# 05-UART.net
KiCad netlist of a schematic drawn in Altium Designer
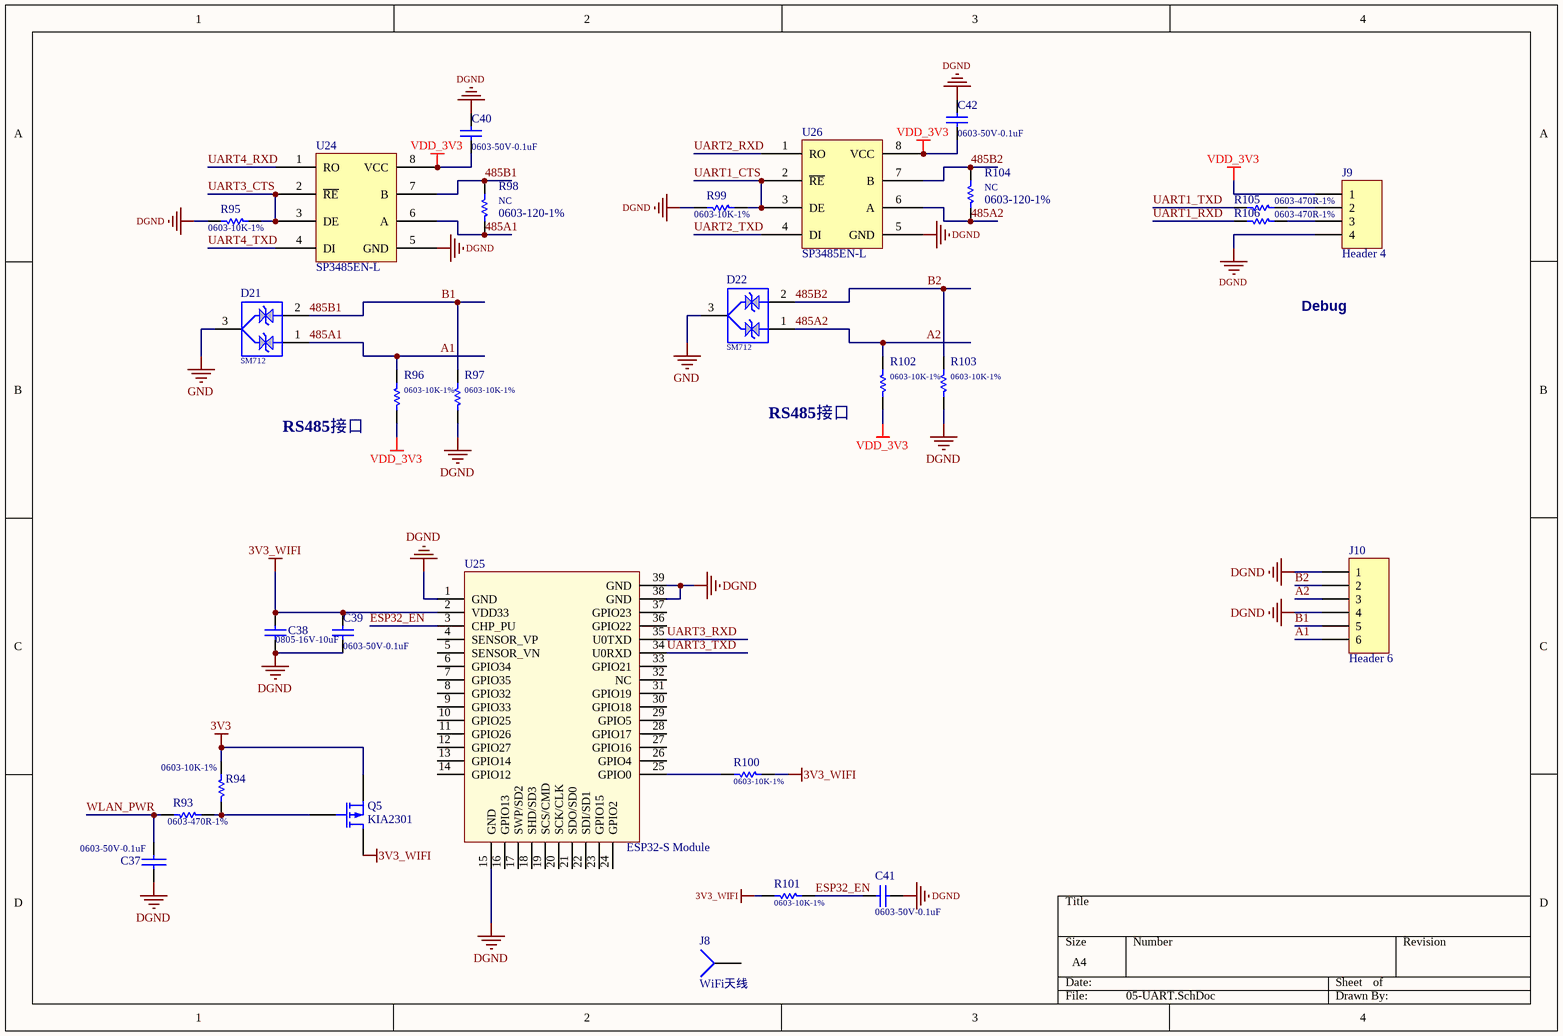
[diagram p0: 05-UART.SchDoc]

(export (version "E")
  (design (tool "Eeschema 10.0.6"))
  (components
    (comp (ref "C37")
      (value "0603-50V-0.1uF")
      (footprint "0603C")
      (description "Capacitor")
      (libsource (lib "*") (part "CAP"))
    )
    (comp (ref "C38")
      (value "0805-16V-10uF")
      (footprint "0805C - 3D")
      (description "Capacitor")
      (fields (field (name "PUBLISHER") "Altium Limited"))
      (libsource (lib "Miscellaneous Devices") (part "Cap"))
    )
    (comp (ref "C39")
      (value "0603-50V-0.1uF")
      (footprint "0603C")
      (description "Capacitor")
      (fields (field (name "PUBLISHER") "Altium Limited"))
      (libsource (lib "Miscellaneous Devices") (part "Cap"))
    )
    (comp (ref "C40")
      (value "0603-50V-0.1uF")
      (footprint "0603C")
      (description "Capacitor")
      (fields (field (name "PUBLISHER") "Altium Limited"))
      (libsource (lib "Miscellaneous Devices") (part "Cap"))
    )
    (comp (ref "C41")
      (value "0603-50V-0.1uF")
      (footprint "0603C")
      (description "Capacitor")
      (fields (field (name "PUBLISHER") "Altium Limited"))
      (libsource (lib "Miscellaneous Devices") (part "Cap"))
    )
    (comp (ref "C42")
      (value "0603-50V-0.1uF")
      (footprint "0603C")
      (description "Capacitor")
      (fields (field (name "PUBLISHER") "Altium Limited"))
      (libsource (lib "Miscellaneous Devices") (part "Cap"))
    )
    (comp (ref "D21")
      (value "SM712")
      (footprint "SOT-23")
      (description "TVS protect")
      (libsource (lib "*") (part "NUP2105L"))
    )
    (comp (ref "D22")
      (value "SM712")
      (footprint "SOT-23")
      (description "TVS protect")
      (libsource (lib "*") (part "NUP2105L"))
    )
    (comp (ref "J8")
      (value "WiFi天线")
      (footprint "SMA-KWE")
      (description "Socket")
      (fields (field (name "PUBLISHER") "Altium Limited"))
      (libsource (lib "Miscellaneous Connectors") (part "Socket"))
    )
    (comp (ref "J9")
      (value "Header 4")
      (footprint "HDR1X4")
      (description "Header, 4-Pin")
      (fields (field (name "PUBLISHER") "Altium Limited"))
      (libsource (lib "Miscellaneous Connectors") (part "Header 4"))
    )
    (comp (ref "J10")
      (value "Header 6")
      (footprint "KF2EDGR-5.08-6P")
      (description "Header, 6-Pin")
      (fields (field (name "PUBLISHER") "Altium Limited"))
      (libsource (lib "Miscellaneous Connectors") (part "Header 6"))
    )
    (comp (ref "Q5")
      (value "KIA2301")
      (footprint "SOT-23")
      (description "P-Channel MOSFET")
      (fields (field (name "PUBLISHER") "Altium Limited"))
      (libsource (lib "fszhang") (part "MOSFET-P"))
    )
    (comp (ref "R93")
      (value "0603-470R-1%")
      (footprint "0603R")
      (description "Resistor")
      (fields (field (name "PUBLISHER") "Altium Limited"))
      (libsource (lib "Miscellaneous Devices") (part "Res1"))
    )
    (comp (ref "R94")
      (value "0603-10K-1%")
      (footprint "0603R")
      (description "Resistor")
      (fields (field (name "PUBLISHER") "Altium Limited"))
      (libsource (lib "Miscellaneous Devices") (part "Res1"))
    )
    (comp (ref "R95")
      (value "0603-10K-1%")
      (footprint "0603R")
      (description "Resistor")
      (fields (field (name "PUBLISHER") "Altium Limited"))
      (libsource (lib "Miscellaneous Devices") (part "Res1"))
    )
    (comp (ref "R96")
      (value "0603-10K-1%")
      (footprint "0603R")
      (description "Resistor")
      (fields (field (name "PUBLISHER") "Altium Limited"))
      (libsource (lib "Miscellaneous Devices") (part "Res1"))
    )
    (comp (ref "R97")
      (value "0603-10K-1%")
      (footprint "0603R")
      (description "Resistor")
      (fields (field (name "PUBLISHER") "Altium Limited"))
      (libsource (lib "Miscellaneous Devices") (part "Res1"))
    )
    (comp (ref "R98")
      (value "NC")
      (footprint "0603R")
      (description "Resistor")
      (fields (field (name "ALTIUM_VALUE") "0603-120-1%") (field (name "PUBLISHER") "Altium Limited"))
      (libsource (lib "Miscellaneous Devices") (part "Res1"))
    )
    (comp (ref "R99")
      (value "0603-10K-1%")
      (footprint "0603R")
      (description "Resistor")
      (fields (field (name "PUBLISHER") "Altium Limited"))
      (libsource (lib "Miscellaneous Devices") (part "Res1"))
    )
    (comp (ref "R100")
      (value "0603-10K-1%")
      (footprint "0603R")
      (description "Resistor")
      (fields (field (name "PUBLISHER") "Altium Limited"))
      (libsource (lib "Miscellaneous Devices") (part "Res1"))
    )
    (comp (ref "R101")
      (value "0603-10K-1%")
      (footprint "0603R")
      (description "Resistor")
      (fields (field (name "PUBLISHER") "Altium Limited"))
      (libsource (lib "Miscellaneous Devices") (part "Res1"))
    )
    (comp (ref "R102")
      (value "0603-10K-1%")
      (footprint "0603R")
      (description "Resistor")
      (fields (field (name "PUBLISHER") "Altium Limited"))
      (libsource (lib "Miscellaneous Devices") (part "Res1"))
    )
    (comp (ref "R103")
      (value "0603-10K-1%")
      (footprint "0603R")
      (description "Resistor")
      (fields (field (name "PUBLISHER") "Altium Limited"))
      (libsource (lib "Miscellaneous Devices") (part "Res1"))
    )
    (comp (ref "R104")
      (value "NC")
      (footprint "0603R")
      (description "Resistor")
      (fields (field (name "ALTIUM_VALUE") "0603-120-1%") (field (name "PUBLISHER") "Altium Limited"))
      (libsource (lib "Miscellaneous Devices") (part "Res1"))
    )
    (comp (ref "R105")
      (value "0603-470R-1%")
      (footprint "0603R")
      (description "Resistor")
      (fields (field (name "PUBLISHER") "Altium Limited"))
      (libsource (lib "Miscellaneous Devices") (part "Res1"))
    )
    (comp (ref "R106")
      (value "0603-470R-1%")
      (footprint "0603R")
      (description "Resistor")
      (fields (field (name "PUBLISHER") "Altium Limited"))
      (libsource (lib "Miscellaneous Devices") (part "Res1"))
    )
    (comp (ref "U24")
      (value "SP3485EN-L")
      (footprint "LC-SOIC-8_150mil")
      (libsource (lib "金龙107原理图封装库") (part "MAX485"))
    )
    (comp (ref "U25")
      (value "ESP32-S Module")
      (footprint "ESP32S")
      (libsource (lib "ESP32-S Module") (part "ESP32-S Module"))
    )
    (comp (ref "U26")
      (value "SP3485EN-L")
      (footprint "LC-SOIC-8_150mil")
      (libsource (lib "金龙107原理图封装库") (part "MAX485"))
    )
  )
  (nets
    (net (code "1") (name "/485A1") (class "Default")
      (node (ref "D21") (pin "1") (pinfunction "1_1") (pintype "passive"))
      (node (ref "J10") (pin "6") (pinfunction "6_6") (pintype "passive"))
      (node (ref "R96") (pin "1") (pinfunction "1_1") (pintype "passive"))
      (node (ref "R98") (pin "2") (pinfunction "2_2") (pintype "passive"))
      (node (ref "U24") (pin "6") (pinfunction "A_6") (pintype "open_emitter"))
    )
    (net (code "2") (name "/485A2") (class "Default")
      (node (ref "D22") (pin "1") (pinfunction "1_1") (pintype "passive"))
      (node (ref "J10") (pin "3") (pinfunction "3_3") (pintype "passive"))
      (node (ref "R102") (pin "1") (pinfunction "1_1") (pintype "passive"))
      (node (ref "R104") (pin "2") (pinfunction "2_2") (pintype "passive"))
      (node (ref "U26") (pin "6") (pinfunction "A_6") (pintype "open_emitter"))
    )
    (net (code "3") (name "/485B1") (class "Default")
      (node (ref "D21") (pin "2") (pinfunction "2_2") (pintype "passive"))
      (node (ref "J10") (pin "5") (pinfunction "5_5") (pintype "passive"))
      (node (ref "R97") (pin "1") (pinfunction "1_1") (pintype "passive"))
      (node (ref "R98") (pin "1") (pinfunction "1_1") (pintype "passive"))
      (node (ref "U24") (pin "7") (pinfunction "B_7") (pintype "open_emitter"))
    )
    (net (code "4") (name "/485B2") (class "Default")
      (node (ref "D22") (pin "2") (pinfunction "2_2") (pintype "passive"))
      (node (ref "J10") (pin "2") (pinfunction "2_2") (pintype "passive"))
      (node (ref "R103") (pin "1") (pinfunction "1_1") (pintype "passive"))
      (node (ref "R104") (pin "1") (pinfunction "1_1") (pintype "passive"))
      (node (ref "U26") (pin "7") (pinfunction "B_7") (pintype "open_emitter"))
    )
    (net (code "5") (name "/ESP32_EN") (class "Default")
      (node (ref "C41") (pin "1") (pinfunction "1_1") (pintype "passive"))
      (node (ref "R101") (pin "1") (pinfunction "1_1") (pintype "passive"))
      (node (ref "U25") (pin "3") (pinfunction "CHP_PU_3") (pintype "passive"))
    )
    (net (code "6") (name "/UART1_CTS") (class "Default")
      (node (ref "R99") (pin "1") (pinfunction "1_1") (pintype "passive"))
      (node (ref "U26") (pin "2") (pinfunction "~{RE}_2") (pintype "passive"))
      (node (ref "U26") (pin "3") (pinfunction "DE_3") (pintype "passive"))
    )
    (net (code "7") (name "/UART1_RXD") (class "Default")
      (node (ref "R106") (pin "2") (pinfunction "2_2") (pintype "passive"))
    )
    (net (code "8") (name "/UART1_TXD") (class "Default")
      (node (ref "R105") (pin "2") (pinfunction "2_2") (pintype "passive"))
    )
    (net (code "9") (name "/UART2_RXD") (class "Default")
      (node (ref "U26") (pin "1") (pinfunction "RO_1") (pintype "open_emitter"))
    )
    (net (code "10") (name "/UART2_TXD") (class "Default")
      (node (ref "U26") (pin "4") (pinfunction "DI_4") (pintype "passive"))
    )
    (net (code "11") (name "/UART3_CTS") (class "Default")
      (node (ref "R95") (pin "1") (pinfunction "1_1") (pintype "passive"))
      (node (ref "U24") (pin "2") (pinfunction "~{RE}_2") (pintype "passive"))
      (node (ref "U24") (pin "3") (pinfunction "DE_3") (pintype "passive"))
    )
    (net (code "12") (name "/UART3_RXD") (class "Default")
      (node (ref "U25") (pin "35") (pinfunction "U0TXD_35") (pintype "passive"))
    )
    (net (code "13") (name "/UART3_TXD") (class "Default")
      (node (ref "U25") (pin "34") (pinfunction "U0RXD_34") (pintype "passive"))
    )
    (net (code "14") (name "/UART4_RXD") (class "Default")
      (node (ref "U24") (pin "1") (pinfunction "RO_1") (pintype "open_emitter"))
    )
    (net (code "15") (name "/UART4_TXD") (class "Default")
      (node (ref "U24") (pin "4") (pinfunction "DI_4") (pintype "passive"))
    )
    (net (code "16") (name "/WLAN_PWR") (class "Default")
      (node (ref "C37") (pin "1") (pinfunction "1_1") (pintype "passive"))
      (node (ref "R93") (pin "2") (pinfunction "2_2") (pintype "passive"))
    )
    (net (code "17") (name "3V3") (class "Default")
      (node (ref "Q5") (pin "S") (pinfunction "S_S") (pintype "passive"))
      (node (ref "R94") (pin "1") (pinfunction "1_1") (pintype "passive"))
    )
    (net (code "18") (name "3V3_WIFI") (class "Default")
      (node (ref "C38") (pin "1") (pinfunction "1_1") (pintype "passive"))
      (node (ref "C39") (pin "1") (pinfunction "1_1") (pintype "passive"))
      (node (ref "Q5") (pin "D") (pinfunction "D_D") (pintype "passive"))
      (node (ref "R100") (pin "2") (pinfunction "2_2") (pintype "passive"))
      (node (ref "R101") (pin "2") (pinfunction "2_2") (pintype "passive"))
      (node (ref "U25") (pin "2") (pinfunction "VDD33_2") (pintype "passive"))
    )
    (net (code "19") (name "DGND") (class "Default")
      (node (ref "C37") (pin "2") (pinfunction "2_2") (pintype "passive"))
      (node (ref "C38") (pin "2") (pinfunction "2_2") (pintype "passive"))
      (node (ref "C39") (pin "2") (pinfunction "2_2") (pintype "passive"))
      (node (ref "C40") (pin "1") (pinfunction "1_1") (pintype "passive"))
      (node (ref "C41") (pin "2") (pinfunction "2_2") (pintype "passive"))
      (node (ref "C42") (pin "1") (pinfunction "1_1") (pintype "passive"))
      (node (ref "J10") (pin "1") (pinfunction "1_1") (pintype "passive"))
      (node (ref "J10") (pin "4") (pinfunction "4_4") (pintype "passive"))
      (node (ref "J9") (pin "4") (pinfunction "4_4") (pintype "passive"))
      (node (ref "R103") (pin "2") (pinfunction "2_2") (pintype "passive"))
      (node (ref "R95") (pin "2") (pinfunction "2_2") (pintype "passive"))
      (node (ref "R97") (pin "2") (pinfunction "2_2") (pintype "passive"))
      (node (ref "R99") (pin "2") (pinfunction "2_2") (pintype "passive"))
      (node (ref "U24") (pin "5") (pinfunction "GND_5") (pintype "passive"))
      (node (ref "U25") (pin "1") (pinfunction "GND_1") (pintype "passive"))
      (node (ref "U25") (pin "15") (pinfunction "GND_15") (pintype "passive"))
      (node (ref "U25") (pin "38") (pinfunction "GND_38") (pintype "passive"))
      (node (ref "U25") (pin "39") (pinfunction "GND_39") (pintype "passive"))
      (node (ref "U26") (pin "5") (pinfunction "GND_5") (pintype "passive"))
    )
    (net (code "20") (name "GND") (class "Default")
      (node (ref "D21") (pin "3") (pinfunction "3_3") (pintype "passive"))
      (node (ref "D22") (pin "3") (pinfunction "3_3") (pintype "passive"))
    )
    (net (code "21") (name "Net-(J9-Pad2)") (class "Default")
      (node (ref "J9") (pin "2") (pinfunction "2_2") (pintype "passive"))
      (node (ref "R105") (pin "1") (pinfunction "1_1") (pintype "passive"))
    )
    (net (code "22") (name "Net-(J9-Pad3)") (class "Default")
      (node (ref "J9") (pin "3") (pinfunction "3_3") (pintype "passive"))
      (node (ref "R106") (pin "1") (pinfunction "1_1") (pintype "passive"))
    )
    (net (code "23") (name "Net-(Q5-PadG)") (class "Default")
      (node (ref "Q5") (pin "G") (pinfunction "G_G") (pintype "passive"))
      (node (ref "R93") (pin "1") (pinfunction "1_1") (pintype "passive"))
      (node (ref "R94") (pin "2") (pinfunction "2_2") (pintype "passive"))
    )
    (net (code "24") (name "Net-(U25-GPIO0)") (class "Default")
      (node (ref "R100") (pin "1") (pinfunction "1_1") (pintype "passive"))
      (node (ref "U25") (pin "25") (pinfunction "GPIO0_25") (pintype "passive"))
    )
    (net (code "25") (name "VDD_3V3") (class "Default")
      (node (ref "C40") (pin "2") (pinfunction "2_2") (pintype "passive"))
      (node (ref "C42") (pin "2") (pinfunction "2_2") (pintype "passive"))
      (node (ref "J9") (pin "1") (pinfunction "1_1") (pintype "passive"))
      (node (ref "R102") (pin "2") (pinfunction "2_2") (pintype "passive"))
      (node (ref "R96") (pin "2") (pinfunction "2_2") (pintype "passive"))
      (node (ref "U24") (pin "8") (pinfunction "VCC_8") (pintype "passive"))
      (node (ref "U26") (pin "8") (pinfunction "VCC_8") (pintype "passive"))
    )
    (net (code "26") (name "unconnected-(J8-Pad1)") (class "Default")
      (node (ref "J8") (pin "1") (pinfunction "1_1") (pintype "passive"))
    )
    (net (code "27") (name "unconnected-(U25-GPIO2-Pad24)") (class "Default")
      (node (ref "U25") (pin "24") (pinfunction "GPIO2_24") (pintype "passive"))
    )
    (net (code "28") (name "unconnected-(U25-GPIO4-Pad26)") (class "Default")
      (node (ref "U25") (pin "26") (pinfunction "GPIO4_26") (pintype "passive"))
    )
    (net (code "29") (name "unconnected-(U25-GPIO5-Pad29)") (class "Default")
      (node (ref "U25") (pin "29") (pinfunction "GPIO5_29") (pintype "passive"))
    )
    (net (code "30") (name "unconnected-(U25-GPIO12-Pad14)") (class "Default")
      (node (ref "U25") (pin "14") (pinfunction "GPIO12_14") (pintype "passive"))
    )
    (net (code "31") (name "unconnected-(U25-GPIO13-Pad16)") (class "Default")
      (node (ref "U25") (pin "16") (pinfunction "GPIO13_16") (pintype "passive"))
    )
    (net (code "32") (name "unconnected-(U25-GPIO14-Pad13)") (class "Default")
      (node (ref "U25") (pin "13") (pinfunction "GPIO14_13") (pintype "passive"))
    )
    (net (code "33") (name "unconnected-(U25-GPIO15-Pad23)") (class "Default")
      (node (ref "U25") (pin "23") (pinfunction "GPIO15_23") (pintype "passive"))
    )
    (net (code "34") (name "unconnected-(U25-GPIO16-Pad27)") (class "Default")
      (node (ref "U25") (pin "27") (pinfunction "GPIO16_27") (pintype "passive"))
    )
    (net (code "35") (name "unconnected-(U25-GPIO17-Pad28)") (class "Default")
      (node (ref "U25") (pin "28") (pinfunction "GPIO17_28") (pintype "passive"))
    )
    (net (code "36") (name "unconnected-(U25-GPIO18-Pad30)") (class "Default")
      (node (ref "U25") (pin "30") (pinfunction "GPIO18_30") (pintype "passive"))
    )
    (net (code "37") (name "unconnected-(U25-GPIO19-Pad31)") (class "Default")
      (node (ref "U25") (pin "31") (pinfunction "GPIO19_31") (pintype "passive"))
    )
    (net (code "38") (name "unconnected-(U25-GPIO21-Pad33)") (class "Default")
      (node (ref "U25") (pin "33") (pinfunction "GPIO21_33") (pintype "passive"))
    )
    (net (code "39") (name "unconnected-(U25-GPIO22-Pad36)") (class "Default")
      (node (ref "U25") (pin "36") (pinfunction "GPIO22_36") (pintype "passive"))
    )
    (net (code "40") (name "unconnected-(U25-GPIO23-Pad37)") (class "Default")
      (node (ref "U25") (pin "37") (pinfunction "GPIO23_37") (pintype "passive"))
    )
    (net (code "41") (name "unconnected-(U25-GPIO25-Pad10)") (class "Default")
      (node (ref "U25") (pin "10") (pinfunction "GPIO25_10") (pintype "passive"))
    )
    (net (code "42") (name "unconnected-(U25-GPIO26-Pad11)") (class "Default")
      (node (ref "U25") (pin "11") (pinfunction "GPIO26_11") (pintype "passive"))
    )
    (net (code "43") (name "unconnected-(U25-GPIO27-Pad12)") (class "Default")
      (node (ref "U25") (pin "12") (pinfunction "GPIO27_12") (pintype "passive"))
    )
    (net (code "44") (name "unconnected-(U25-GPIO32-Pad8)") (class "Default")
      (node (ref "U25") (pin "8") (pinfunction "GPIO32_8") (pintype "passive"))
    )
    (net (code "45") (name "unconnected-(U25-GPIO33-Pad9)") (class "Default")
      (node (ref "U25") (pin "9") (pinfunction "GPIO33_9") (pintype "passive"))
    )
    (net (code "46") (name "unconnected-(U25-GPIO34-Pad6)") (class "Default")
      (node (ref "U25") (pin "6") (pinfunction "GPIO34_6") (pintype "passive"))
    )
    (net (code "47") (name "unconnected-(U25-GPIO35-Pad7)") (class "Default")
      (node (ref "U25") (pin "7") (pinfunction "GPIO35_7") (pintype "passive"))
    )
    (net (code "48") (name "unconnected-(U25-NC-Pad32)") (class "Default")
      (node (ref "U25") (pin "32") (pinfunction "NC_32") (pintype "passive"))
    )
    (net (code "49") (name "unconnected-(U25-SCK{slash}CLK-Pad20)") (class "Default")
      (node (ref "U25") (pin "20") (pinfunction "SCK/CLK_20") (pintype "passive"))
    )
    (net (code "50") (name "unconnected-(U25-SCS{slash}CMD-Pad19)") (class "Default")
      (node (ref "U25") (pin "19") (pinfunction "SCS/CMD_19") (pintype "passive"))
    )
    (net (code "51") (name "unconnected-(U25-SDI{slash}SD1-Pad22)") (class "Default")
      (node (ref "U25") (pin "22") (pinfunction "SDI/SD1_22") (pintype "passive"))
    )
    (net (code "52") (name "unconnected-(U25-SDO{slash}SD0-Pad21)") (class "Default")
      (node (ref "U25") (pin "21") (pinfunction "SDO/SD0_21") (pintype "passive"))
    )
    (net (code "53") (name "unconnected-(U25-SENSOR_VN-Pad5)") (class "Default")
      (node (ref "U25") (pin "5") (pinfunction "SENSOR_VN_5") (pintype "passive"))
    )
    (net (code "54") (name "unconnected-(U25-SENSOR_VP-Pad4)") (class "Default")
      (node (ref "U25") (pin "4") (pinfunction "SENSOR_VP_4") (pintype "passive"))
    )
    (net (code "55") (name "unconnected-(U25-SHD{slash}SD3-Pad18)") (class "Default")
      (node (ref "U25") (pin "18") (pinfunction "SHD/SD3_18") (pintype "passive"))
    )
    (net (code "56") (name "unconnected-(U25-SWP{slash}SD2-Pad17)") (class "Default")
      (node (ref "U25") (pin "17") (pinfunction "SWP/SD2_17") (pintype "passive"))
    )
  )
)
